# new_remote_pcb.net
KiCad netlist of a schematic drawn in EAGLE
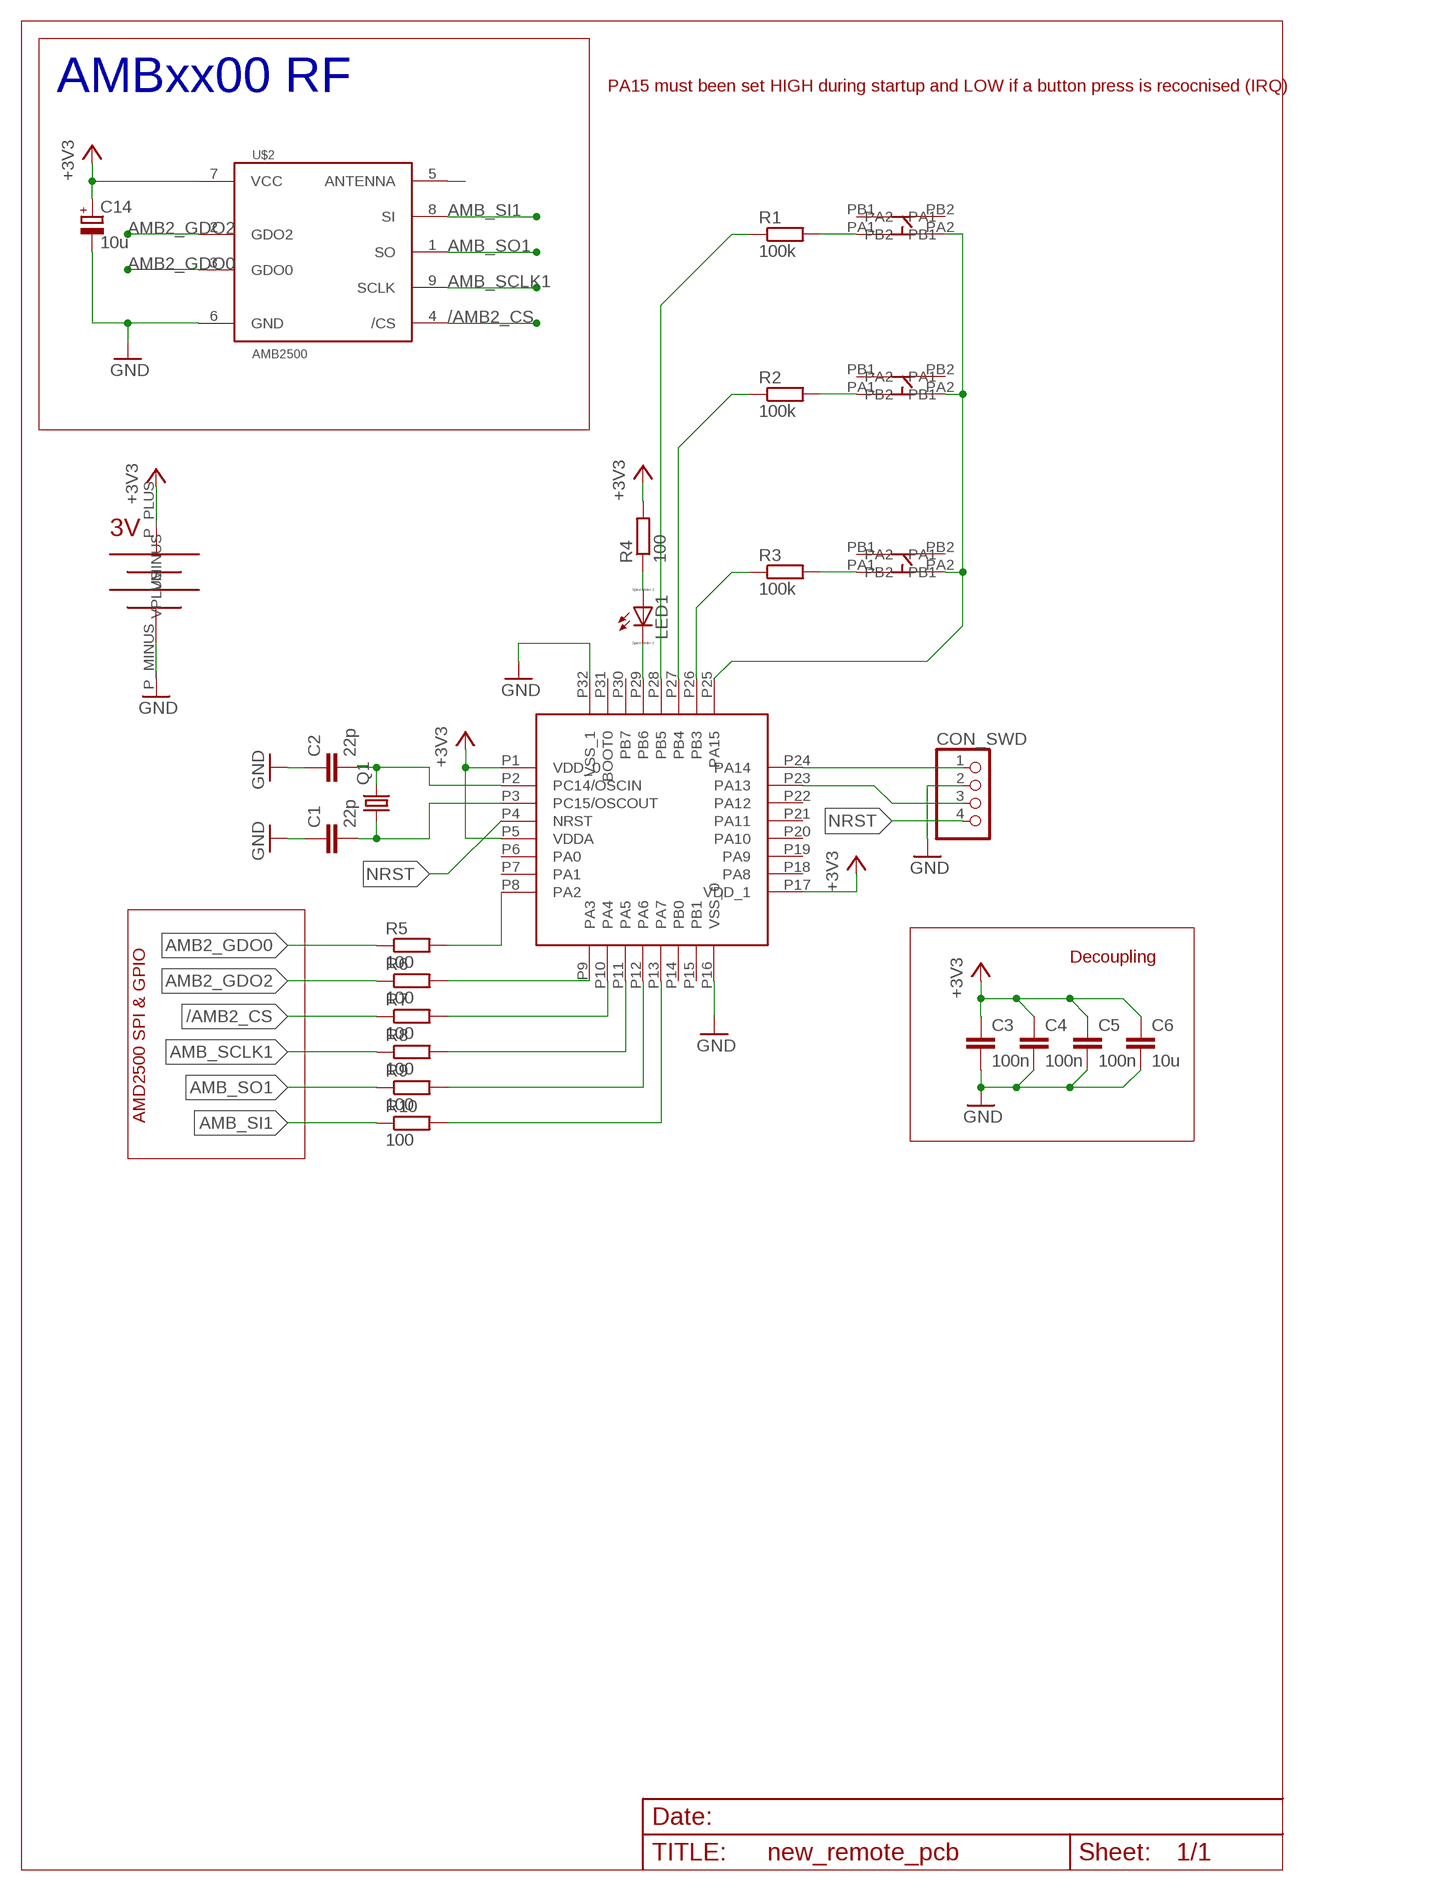
[diagram p0: schematic, sheet 1]

(export (version "E")
  (design (tool "Eeschema 10.0.6"))
  (components
    (comp (ref "C1")
      (value "22p")
      (footprint "eagle-import:C0805K")
      (libsource (lib "eagle-import") (part "C-EUC0805K"))
    )
    (comp (ref "C2")
      (value "22p")
      (footprint "eagle-import:C0805K")
      (libsource (lib "eagle-import") (part "C-EUC0805K"))
    )
    (comp (ref "C3")
      (value "100n")
      (footprint "eagle-import:C0805")
      (libsource (lib "eagle-import") (part "resistor_C-EUC0805"))
    )
    (comp (ref "C4")
      (value "100n")
      (footprint "eagle-import:C0805")
      (libsource (lib "eagle-import") (part "resistor_C-EUC0805"))
    )
    (comp (ref "C5")
      (value "100n")
      (footprint "eagle-import:C0805")
      (libsource (lib "eagle-import") (part "resistor_C-EUC0805"))
    )
    (comp (ref "C6")
      (value "10u")
      (footprint "eagle-import:C0805")
      (libsource (lib "eagle-import") (part "resistor_C-EUC0805"))
    )
    (comp (ref "C14")
      (value "10u")
      (footprint "eagle-import:A_3216-18W")
      (libsource (lib "eagle-import") (part "CPOL-EUA/3216-18W"))
    )
    (comp (ref "CON_SWD")
      (value "PINHD-1X4")
      (footprint "eagle-import:1X04")
      (libsource (lib "eagle-import") (part "PINHD-1X4"))
    )
    (comp (ref "LED1")
      (value "LED_E")
      (footprint "eagle-import:LED_1206")
      (libsource (lib "eagle-import") (part "LED_E"))
    )
    (comp (ref "Q1")
      (value "CRYSTALHC49UP")
      (footprint "eagle-import:HC49UP")
      (libsource (lib "eagle-import") (part "CRYSTALHC49UP"))
    )
    (comp (ref "R1")
      (value "100k")
      (footprint "eagle-import:R0805W")
      (libsource (lib "eagle-import") (part "R-EU_R0805W"))
    )
    (comp (ref "R2")
      (value "100k")
      (footprint "eagle-import:R0805W")
      (libsource (lib "eagle-import") (part "R-EU_R0805W"))
    )
    (comp (ref "R3")
      (value "100k")
      (footprint "eagle-import:R0805W")
      (libsource (lib "eagle-import") (part "R-EU_R0805W"))
    )
    (comp (ref "R4")
      (value "100")
      (footprint "eagle-import:R0805W")
      (libsource (lib "eagle-import") (part "R-EU_R0805W"))
    )
    (comp (ref "R5")
      (value "100")
      (footprint "eagle-import:R0805")
      (libsource (lib "eagle-import") (part "resistor_R-EU_R0805"))
    )
    (comp (ref "R6")
      (value "100")
      (footprint "eagle-import:R0805")
      (libsource (lib "eagle-import") (part "resistor_R-EU_R0805"))
    )
    (comp (ref "R7")
      (value "100")
      (footprint "eagle-import:R0805")
      (libsource (lib "eagle-import") (part "resistor_R-EU_R0805"))
    )
    (comp (ref "R8")
      (value "100")
      (footprint "eagle-import:R0805")
      (libsource (lib "eagle-import") (part "resistor_R-EU_R0805"))
    )
    (comp (ref "R9")
      (value "100")
      (footprint "eagle-import:R0805")
      (libsource (lib "eagle-import") (part "resistor_R-EU_R0805"))
    )
    (comp (ref "R10")
      (value "100")
      (footprint "eagle-import:R0805")
      (libsource (lib "eagle-import") (part "resistor_R-EU_R0805"))
    )
    (comp (ref "U$1")
      (value "STM32L051K8T6")
      (footprint "eagle-import:LQFP32")
      (libsource (lib "eagle-import") (part "STM32L051K8T6"))
    )
    (comp (ref "U$2")
      (value "AMB2500")
      (footprint "eagle-import:AMB8400")
      (libsource (lib "eagle-import") (part "AMB8400"))
    )
    (comp (ref "U$3")
      (value "KEYSTONE_2462")
      (footprint "eagle-import:2462")
      (libsource (lib "eagle-import") (part "KEYSTONE_2462"))
    )
    (comp (ref "U$4")
      (value "C&K_KSC_BUTTONS")
      (footprint "eagle-import:C&K_KSC9")
      (libsource (lib "eagle-import") (part "C&K_KSC_BUTTONS"))
    )
    (comp (ref "U$5")
      (value "C&K_KSC_BUTTONS")
      (footprint "eagle-import:C&K_KSC9")
      (libsource (lib "eagle-import") (part "C&K_KSC_BUTTONS"))
    )
    (comp (ref "U$6")
      (value "C&K_KSC_BUTTONS")
      (footprint "eagle-import:C&K_KSC9")
      (libsource (lib "eagle-import") (part "C&K_KSC_BUTTONS"))
    )
  )
  (nets
    (net (code "1") (name "+3V3") (class "Default")
      (node (ref "C14") (pin "+") (pinfunction "+_+") (pintype "passive"))
      (node (ref "C3") (pin "1") (pinfunction "1_1") (pintype "passive"))
      (node (ref "C4") (pin "1") (pinfunction "1_1") (pintype "passive"))
      (node (ref "C5") (pin "1") (pinfunction "1_1") (pintype "passive"))
      (node (ref "C6") (pin "1") (pinfunction "1_1") (pintype "passive"))
      (node (ref "R4") (pin "2") (pinfunction "2_2") (pintype "passive"))
      (node (ref "U$1") (pin "P1") (pinfunction "VDD_0_P1") (pintype "bidirectional"))
      (node (ref "U$1") (pin "P17") (pinfunction "VDD_1_P17") (pintype "bidirectional"))
      (node (ref "U$1") (pin "P5") (pinfunction "VDDA_P5") (pintype "bidirectional"))
      (node (ref "U$2") (pin "7") (pinfunction "VCC_7") (pintype "power_in"))
      (node (ref "U$3") (pin "P_PLUS") (pinfunction "VPLUS_P_PLUS") (pintype "bidirectional"))
    )
    (net (code "2") (name "AMB2_GDO0") (class "Default")
      (node (ref "R5") (pin "1") (pinfunction "1_1") (pintype "passive"))
      (node (ref "U$2") (pin "3") (pinfunction "GDO0_3") (pintype "output"))
    )
    (net (code "3") (name "AMB2_GDO2") (class "Default")
      (node (ref "R6") (pin "1") (pinfunction "1_1") (pintype "passive"))
      (node (ref "U$2") (pin "2") (pinfunction "GDO2_2") (pintype "output"))
    )
    (net (code "4") (name "AMB_SCLK1") (class "Default")
      (node (ref "R8") (pin "1") (pinfunction "1_1") (pintype "passive"))
      (node (ref "U$2") (pin "9") (pinfunction "SCLK_9") (pintype "input"))
    )
    (net (code "5") (name "AMB_SI1") (class "Default")
      (node (ref "R10") (pin "1") (pinfunction "1_1") (pintype "passive"))
      (node (ref "U$2") (pin "8") (pinfunction "SI_8") (pintype "input"))
    )
    (net (code "6") (name "AMB_SO1") (class "Default")
      (node (ref "R9") (pin "1") (pinfunction "1_1") (pintype "passive"))
      (node (ref "U$2") (pin "1") (pinfunction "SO_1") (pintype "output"))
    )
    (net (code "7") (name "GND") (class "Default")
      (node (ref "C1") (pin "1") (pinfunction "1_1") (pintype "passive"))
      (node (ref "C14") (pin "-") (pinfunction "-_-") (pintype "passive"))
      (node (ref "C2") (pin "1") (pinfunction "1_1") (pintype "passive"))
      (node (ref "C3") (pin "2") (pinfunction "2_2") (pintype "passive"))
      (node (ref "C4") (pin "2") (pinfunction "2_2") (pintype "passive"))
      (node (ref "C5") (pin "2") (pinfunction "2_2") (pintype "passive"))
      (node (ref "C6") (pin "2") (pinfunction "2_2") (pintype "passive"))
      (node (ref "CON_SWD") (pin "2") (pinfunction "2_2") (pintype "passive"))
      (node (ref "U$1") (pin "P16") (pinfunction "VSS_0_P16") (pintype "bidirectional"))
      (node (ref "U$1") (pin "P32") (pinfunction "VSS_1_P32") (pintype "bidirectional"))
      (node (ref "U$2") (pin "6") (pinfunction "GND_6") (pintype "power_in"))
      (node (ref "U$3") (pin "P_MINUS") (pinfunction "VMINUS_P_MINUS") (pintype "bidirectional"))
    )
    (net (code "8") (name "NRST") (class "Default")
      (node (ref "CON_SWD") (pin "4") (pinfunction "4_4") (pintype "passive"))
      (node (ref "U$1") (pin "P4") (pinfunction "NRST_P4") (pintype "bidirectional"))
    )
    (net (code "9") (name "Net-(LED1-PadA)") (class "Default")
      (node (ref "LED1") (pin "A") (pinfunction "A_A") (pintype "passive"))
      (node (ref "R4") (pin "1") (pinfunction "1_1") (pintype "passive"))
    )
    (net (code "10") (name "Net-(U$1-PA2)") (class "Default")
      (node (ref "R5") (pin "2") (pinfunction "2_2") (pintype "passive"))
      (node (ref "U$1") (pin "P8") (pinfunction "PA2_P8") (pintype "bidirectional"))
    )
    (net (code "11") (name "Net-(U$1-PA3)") (class "Default")
      (node (ref "R6") (pin "2") (pinfunction "2_2") (pintype "passive"))
      (node (ref "U$1") (pin "P9") (pinfunction "PA3_P9") (pintype "bidirectional"))
    )
    (net (code "12") (name "Net-(U$1-PA4)") (class "Default")
      (node (ref "R7") (pin "2") (pinfunction "2_2") (pintype "passive"))
      (node (ref "U$1") (pin "P10") (pinfunction "PA4_P10") (pintype "bidirectional"))
    )
    (net (code "13") (name "Net-(U$1-PA5)") (class "Default")
      (node (ref "R8") (pin "2") (pinfunction "2_2") (pintype "passive"))
      (node (ref "U$1") (pin "P11") (pinfunction "PA5_P11") (pintype "bidirectional"))
    )
    (net (code "14") (name "Net-(U$1-PA6)") (class "Default")
      (node (ref "R9") (pin "2") (pinfunction "2_2") (pintype "passive"))
      (node (ref "U$1") (pin "P12") (pinfunction "PA6_P12") (pintype "bidirectional"))
    )
    (net (code "15") (name "Net-(U$1-PA7)") (class "Default")
      (node (ref "R10") (pin "2") (pinfunction "2_2") (pintype "passive"))
      (node (ref "U$1") (pin "P13") (pinfunction "PA7_P13") (pintype "bidirectional"))
    )
    (net (code "16") (name "Net-(U$1-PA13)") (class "Default")
      (node (ref "CON_SWD") (pin "3") (pinfunction "3_3") (pintype "passive"))
      (node (ref "U$1") (pin "P23") (pinfunction "PA13_P23") (pintype "bidirectional"))
    )
    (net (code "17") (name "Net-(U$1-PA14)") (class "Default")
      (node (ref "CON_SWD") (pin "1") (pinfunction "1_1") (pintype "passive"))
      (node (ref "U$1") (pin "P24") (pinfunction "PA14_P24") (pintype "bidirectional"))
    )
    (net (code "18") (name "Net-(U$1-PA15)") (class "Default")
      (node (ref "U$1") (pin "P25") (pinfunction "PA15_P25") (pintype "bidirectional"))
      (node (ref "U$4") (pin "PA2") (pinfunction "PB2_PA2") (pintype "bidirectional"))
      (node (ref "U$5") (pin "PA2") (pinfunction "PB2_PA2") (pintype "bidirectional"))
      (node (ref "U$6") (pin "PA2") (pinfunction "PB2_PA2") (pintype "bidirectional"))
    )
    (net (code "19") (name "Net-(U$1-PB3)") (class "Default")
      (node (ref "R3") (pin "1") (pinfunction "1_1") (pintype "passive"))
      (node (ref "U$1") (pin "P26") (pinfunction "PB3_P26") (pintype "bidirectional"))
    )
    (net (code "20") (name "Net-(U$1-PB4)") (class "Default")
      (node (ref "R2") (pin "1") (pinfunction "1_1") (pintype "passive"))
      (node (ref "U$1") (pin "P27") (pinfunction "PB4_P27") (pintype "bidirectional"))
    )
    (net (code "21") (name "Net-(U$1-PB5)") (class "Default")
      (node (ref "R1") (pin "1") (pinfunction "1_1") (pintype "passive"))
      (node (ref "U$1") (pin "P28") (pinfunction "PB5_P28") (pintype "bidirectional"))
    )
    (net (code "22") (name "Net-(U$1-PB6)") (class "Default")
      (node (ref "LED1") (pin "C") (pinfunction "C_C") (pintype "passive"))
      (node (ref "U$1") (pin "P29") (pinfunction "PB6_P29") (pintype "bidirectional"))
    )
    (net (code "23") (name "Net-(U$1-PC14{slash}OSCIN)") (class "Default")
      (node (ref "C2") (pin "2") (pinfunction "2_2") (pintype "passive"))
      (node (ref "Q1") (pin "2") (pinfunction "2_2") (pintype "passive"))
      (node (ref "U$1") (pin "P2") (pinfunction "PC14/OSCIN_P2") (pintype "bidirectional"))
    )
    (net (code "24") (name "Net-(U$1-PC15{slash}OSCOUT)") (class "Default")
      (node (ref "C1") (pin "2") (pinfunction "2_2") (pintype "passive"))
      (node (ref "Q1") (pin "1") (pinfunction "1_1") (pintype "passive"))
      (node (ref "U$1") (pin "P3") (pinfunction "PC15/OSCOUT_P3") (pintype "bidirectional"))
    )
    (net (code "25") (name "Net-(U$4-PB1)") (class "Default")
      (node (ref "R1") (pin "2") (pinfunction "2_2") (pintype "passive"))
      (node (ref "U$4") (pin "PA1") (pinfunction "PB1_PA1") (pintype "bidirectional"))
    )
    (net (code "26") (name "Net-(U$5-PB1)") (class "Default")
      (node (ref "R2") (pin "2") (pinfunction "2_2") (pintype "passive"))
      (node (ref "U$5") (pin "PA1") (pinfunction "PB1_PA1") (pintype "bidirectional"))
    )
    (net (code "27") (name "Net-(U$6-PB1)") (class "Default")
      (node (ref "R3") (pin "2") (pinfunction "2_2") (pintype "passive"))
      (node (ref "U$6") (pin "PA1") (pinfunction "PB1_PA1") (pintype "bidirectional"))
    )
    (net (code "28") (name "unconnected-(U$1-BOOT0-PadP31)") (class "Default")
      (node (ref "U$1") (pin "P31") (pinfunction "BOOT0_P31") (pintype "bidirectional"))
    )
    (net (code "29") (name "unconnected-(U$1-PA0-PadP6)") (class "Default")
      (node (ref "U$1") (pin "P6") (pinfunction "PA0_P6") (pintype "bidirectional"))
    )
    (net (code "30") (name "unconnected-(U$1-PA1-PadP7)") (class "Default")
      (node (ref "U$1") (pin "P7") (pinfunction "PA1_P7") (pintype "bidirectional"))
    )
    (net (code "31") (name "unconnected-(U$1-PA8-PadP18)") (class "Default")
      (node (ref "U$1") (pin "P18") (pinfunction "PA8_P18") (pintype "bidirectional"))
    )
    (net (code "32") (name "unconnected-(U$1-PA9-PadP19)") (class "Default")
      (node (ref "U$1") (pin "P19") (pinfunction "PA9_P19") (pintype "bidirectional"))
    )
    (net (code "33") (name "unconnected-(U$1-PA10-PadP20)") (class "Default")
      (node (ref "U$1") (pin "P20") (pinfunction "PA10_P20") (pintype "bidirectional"))
    )
    (net (code "34") (name "unconnected-(U$1-PA11-PadP21)") (class "Default")
      (node (ref "U$1") (pin "P21") (pinfunction "PA11_P21") (pintype "bidirectional"))
    )
    (net (code "35") (name "unconnected-(U$1-PA12-PadP22)") (class "Default")
      (node (ref "U$1") (pin "P22") (pinfunction "PA12_P22") (pintype "bidirectional"))
    )
    (net (code "36") (name "unconnected-(U$1-PB0-PadP14)") (class "Default")
      (node (ref "U$1") (pin "P14") (pinfunction "PB0_P14") (pintype "bidirectional"))
    )
    (net (code "37") (name "unconnected-(U$1-PB1-PadP15)") (class "Default")
      (node (ref "U$1") (pin "P15") (pinfunction "PB1_P15") (pintype "bidirectional"))
    )
    (net (code "38") (name "unconnected-(U$1-PB7-PadP30)") (class "Default")
      (node (ref "U$1") (pin "P30") (pinfunction "PB7_P30") (pintype "bidirectional"))
    )
    (net (code "39") (name "unconnected-(U$2-ANTENNA-Pad5)") (class "Default")
      (node (ref "U$2") (pin "5") (pinfunction "ANTENNA_5") (pintype "output"))
    )
    (net (code "40") (name "unconnected-(U$4-PA1-PadPB1)") (class "Default")
      (node (ref "U$4") (pin "PB1") (pinfunction "PA1_PB1") (pintype "bidirectional"))
    )
    (net (code "41") (name "unconnected-(U$4-PA2-PadPB2)") (class "Default")
      (node (ref "U$4") (pin "PB2") (pinfunction "PA2_PB2") (pintype "bidirectional"))
    )
    (net (code "42") (name "unconnected-(U$5-PA1-PadPB1)") (class "Default")
      (node (ref "U$5") (pin "PB1") (pinfunction "PA1_PB1") (pintype "bidirectional"))
    )
    (net (code "43") (name "unconnected-(U$5-PA2-PadPB2)") (class "Default")
      (node (ref "U$5") (pin "PB2") (pinfunction "PA2_PB2") (pintype "bidirectional"))
    )
    (net (code "44") (name "unconnected-(U$6-PA1-PadPB1)") (class "Default")
      (node (ref "U$6") (pin "PB1") (pinfunction "PA1_PB1") (pintype "bidirectional"))
    )
    (net (code "45") (name "unconnected-(U$6-PA2-PadPB2)") (class "Default")
      (node (ref "U$6") (pin "PB2") (pinfunction "PA2_PB2") (pintype "bidirectional"))
    )
    (net (code "46") (name "{slash}AMB2_CS") (class "Default")
      (node (ref "R7") (pin "1") (pinfunction "1_1") (pintype "passive"))
      (node (ref "U$2") (pin "4") (pinfunction "/CS_4") (pintype "input"))
    )
  )
)
